# QFN-24_to_DIP-24.net
KiCad netlist of a schematic drawn in EAGLE
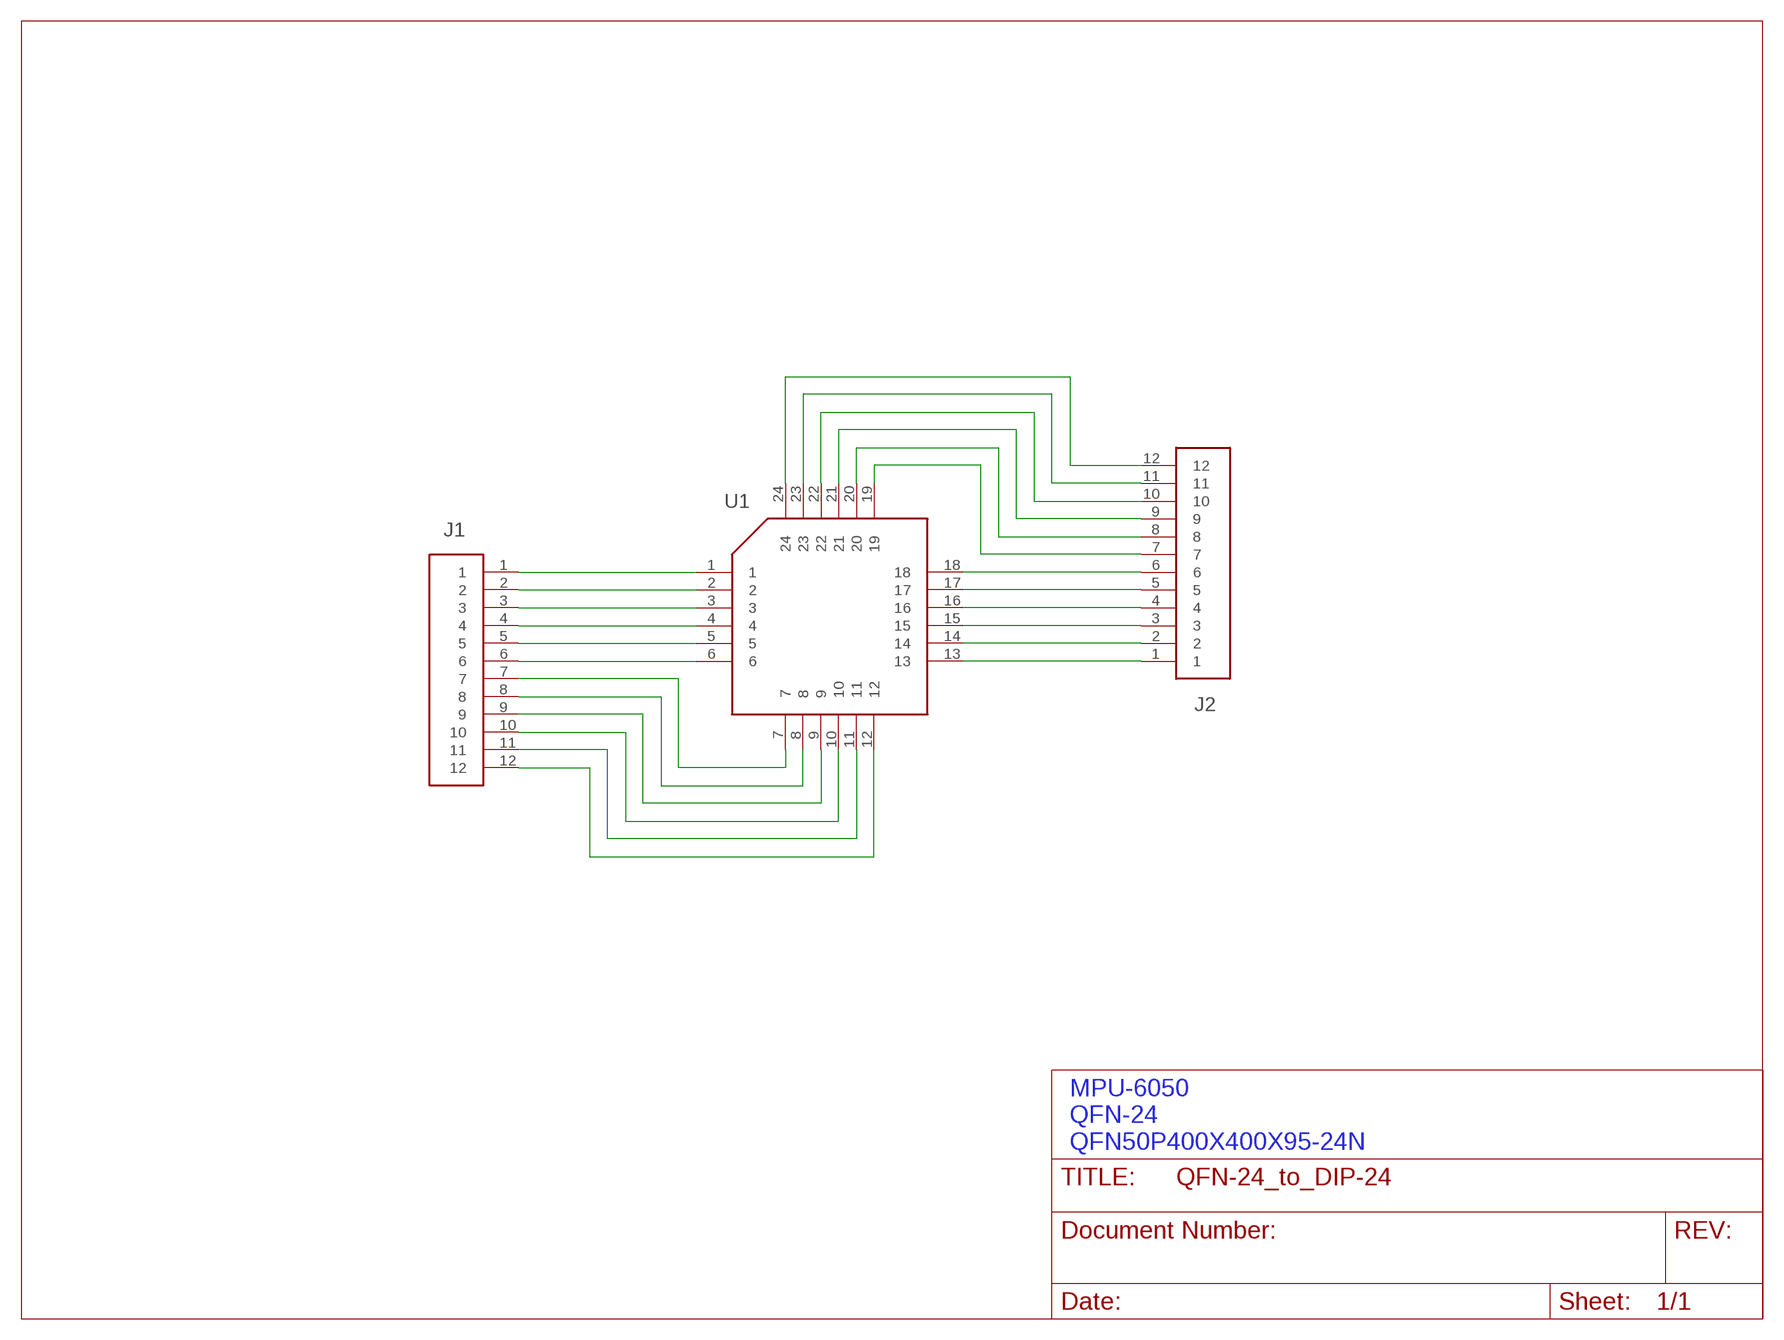
[diagram p0: schematic, sheet 1]

(export (version "E")
  (design (tool "Eeschema 10.0.6"))
  (components
    (comp (ref "J1")
      (value "CONNECTOR_12")
      (footprint "eagle-import:68000-112HLF")
      (libsource (lib "eagle-import") (part "CONNECTOR_12"))
    )
    (comp (ref "J2")
      (value "CONNECTOR_12-NO_SQUARE")
      (footprint "eagle-import:68000-112HLF_NO_SQUARE")
      (libsource (lib "eagle-import") (part "CONNECTOR_12-NO_SQUARE"))
    )
    (comp (ref "U1")
      (value "IC_GENERIC_24-QFN24-NO-EP")
      (footprint "eagle-import:QFN50P400X400X95-24N")
      (libsource (lib "eagle-import") (part "IC_GENERIC_24-QFN24-NO-EP"))
    )
  )
  (nets
    (net (code "1") (name "Net-(J1-Pad1)") (class "Default")
      (node (ref "J1") (pin "1") (pinfunction "1_1") (pintype "bidirectional"))
      (node (ref "U1") (pin "1") (pinfunction "1_1") (pintype "bidirectional"))
    )
    (net (code "2") (name "Net-(J1-Pad2)") (class "Default")
      (node (ref "J1") (pin "2") (pinfunction "2_2") (pintype "bidirectional"))
      (node (ref "U1") (pin "2") (pinfunction "2_2") (pintype "bidirectional"))
    )
    (net (code "3") (name "Net-(J1-Pad3)") (class "Default")
      (node (ref "J1") (pin "3") (pinfunction "3_3") (pintype "bidirectional"))
      (node (ref "U1") (pin "3") (pinfunction "3_3") (pintype "bidirectional"))
    )
    (net (code "4") (name "Net-(J1-Pad4)") (class "Default")
      (node (ref "J1") (pin "4") (pinfunction "4_4") (pintype "bidirectional"))
      (node (ref "U1") (pin "4") (pinfunction "4_4") (pintype "bidirectional"))
    )
    (net (code "5") (name "Net-(J1-Pad5)") (class "Default")
      (node (ref "J1") (pin "5") (pinfunction "5_5") (pintype "bidirectional"))
      (node (ref "U1") (pin "5") (pinfunction "5_5") (pintype "bidirectional"))
    )
    (net (code "6") (name "Net-(J1-Pad6)") (class "Default")
      (node (ref "J1") (pin "6") (pinfunction "6_6") (pintype "bidirectional"))
      (node (ref "U1") (pin "6") (pinfunction "6_6") (pintype "bidirectional"))
    )
    (net (code "7") (name "Net-(J1-Pad7)") (class "Default")
      (node (ref "J1") (pin "7") (pinfunction "7_7") (pintype "bidirectional"))
      (node (ref "U1") (pin "7") (pinfunction "7_7") (pintype "bidirectional"))
    )
    (net (code "8") (name "Net-(J1-Pad8)") (class "Default")
      (node (ref "J1") (pin "8") (pinfunction "8_8") (pintype "bidirectional"))
      (node (ref "U1") (pin "8") (pinfunction "8_8") (pintype "bidirectional"))
    )
    (net (code "9") (name "Net-(J1-Pad9)") (class "Default")
      (node (ref "J1") (pin "9") (pinfunction "9_9") (pintype "bidirectional"))
      (node (ref "U1") (pin "9") (pinfunction "9_9") (pintype "bidirectional"))
    )
    (net (code "10") (name "Net-(J1-Pad10)") (class "Default")
      (node (ref "J1") (pin "10") (pinfunction "10_10") (pintype "bidirectional"))
      (node (ref "U1") (pin "10") (pinfunction "10_10") (pintype "bidirectional"))
    )
    (net (code "11") (name "Net-(J1-Pad11)") (class "Default")
      (node (ref "J1") (pin "11") (pinfunction "11_11") (pintype "bidirectional"))
      (node (ref "U1") (pin "11") (pinfunction "11_11") (pintype "bidirectional"))
    )
    (net (code "12") (name "Net-(J1-Pad12)") (class "Default")
      (node (ref "J1") (pin "12") (pinfunction "12_12") (pintype "bidirectional"))
      (node (ref "U1") (pin "12") (pinfunction "12_12") (pintype "bidirectional"))
    )
    (net (code "13") (name "Net-(J2-Pad1)") (class "Default")
      (node (ref "J2") (pin "1") (pinfunction "1_1") (pintype "bidirectional"))
      (node (ref "U1") (pin "13") (pinfunction "13_13") (pintype "bidirectional"))
    )
    (net (code "14") (name "Net-(J2-Pad2)") (class "Default")
      (node (ref "J2") (pin "2") (pinfunction "2_2") (pintype "bidirectional"))
      (node (ref "U1") (pin "14") (pinfunction "14_14") (pintype "bidirectional"))
    )
    (net (code "15") (name "Net-(J2-Pad3)") (class "Default")
      (node (ref "J2") (pin "3") (pinfunction "3_3") (pintype "bidirectional"))
      (node (ref "U1") (pin "15") (pinfunction "15_15") (pintype "bidirectional"))
    )
    (net (code "16") (name "Net-(J2-Pad4)") (class "Default")
      (node (ref "J2") (pin "4") (pinfunction "4_4") (pintype "bidirectional"))
      (node (ref "U1") (pin "16") (pinfunction "16_16") (pintype "bidirectional"))
    )
    (net (code "17") (name "Net-(J2-Pad5)") (class "Default")
      (node (ref "J2") (pin "5") (pinfunction "5_5") (pintype "bidirectional"))
      (node (ref "U1") (pin "17") (pinfunction "17_17") (pintype "bidirectional"))
    )
    (net (code "18") (name "Net-(J2-Pad6)") (class "Default")
      (node (ref "J2") (pin "6") (pinfunction "6_6") (pintype "bidirectional"))
      (node (ref "U1") (pin "18") (pinfunction "18_18") (pintype "bidirectional"))
    )
    (net (code "19") (name "Net-(J2-Pad7)") (class "Default")
      (node (ref "J2") (pin "7") (pinfunction "7_7") (pintype "bidirectional"))
      (node (ref "U1") (pin "19") (pinfunction "19_19") (pintype "bidirectional"))
    )
    (net (code "20") (name "Net-(J2-Pad8)") (class "Default")
      (node (ref "J2") (pin "8") (pinfunction "8_8") (pintype "bidirectional"))
      (node (ref "U1") (pin "20") (pinfunction "20_20") (pintype "bidirectional"))
    )
    (net (code "21") (name "Net-(J2-Pad9)") (class "Default")
      (node (ref "J2") (pin "9") (pinfunction "9_9") (pintype "bidirectional"))
      (node (ref "U1") (pin "21") (pinfunction "21_21") (pintype "bidirectional"))
    )
    (net (code "22") (name "Net-(J2-Pad10)") (class "Default")
      (node (ref "J2") (pin "10") (pinfunction "10_10") (pintype "bidirectional"))
      (node (ref "U1") (pin "22") (pinfunction "22_22") (pintype "bidirectional"))
    )
    (net (code "23") (name "Net-(J2-Pad11)") (class "Default")
      (node (ref "J2") (pin "11") (pinfunction "11_11") (pintype "bidirectional"))
      (node (ref "U1") (pin "23") (pinfunction "23_23") (pintype "bidirectional"))
    )
    (net (code "24") (name "Net-(J2-Pad12)") (class "Default")
      (node (ref "J2") (pin "12") (pinfunction "12_12") (pintype "bidirectional"))
      (node (ref "U1") (pin "24") (pinfunction "24_24") (pintype "bidirectional"))
    )
  )
)
